# WS2812_MATRIX_9.net
KiCad netlist of a schematic drawn in Altium Designer
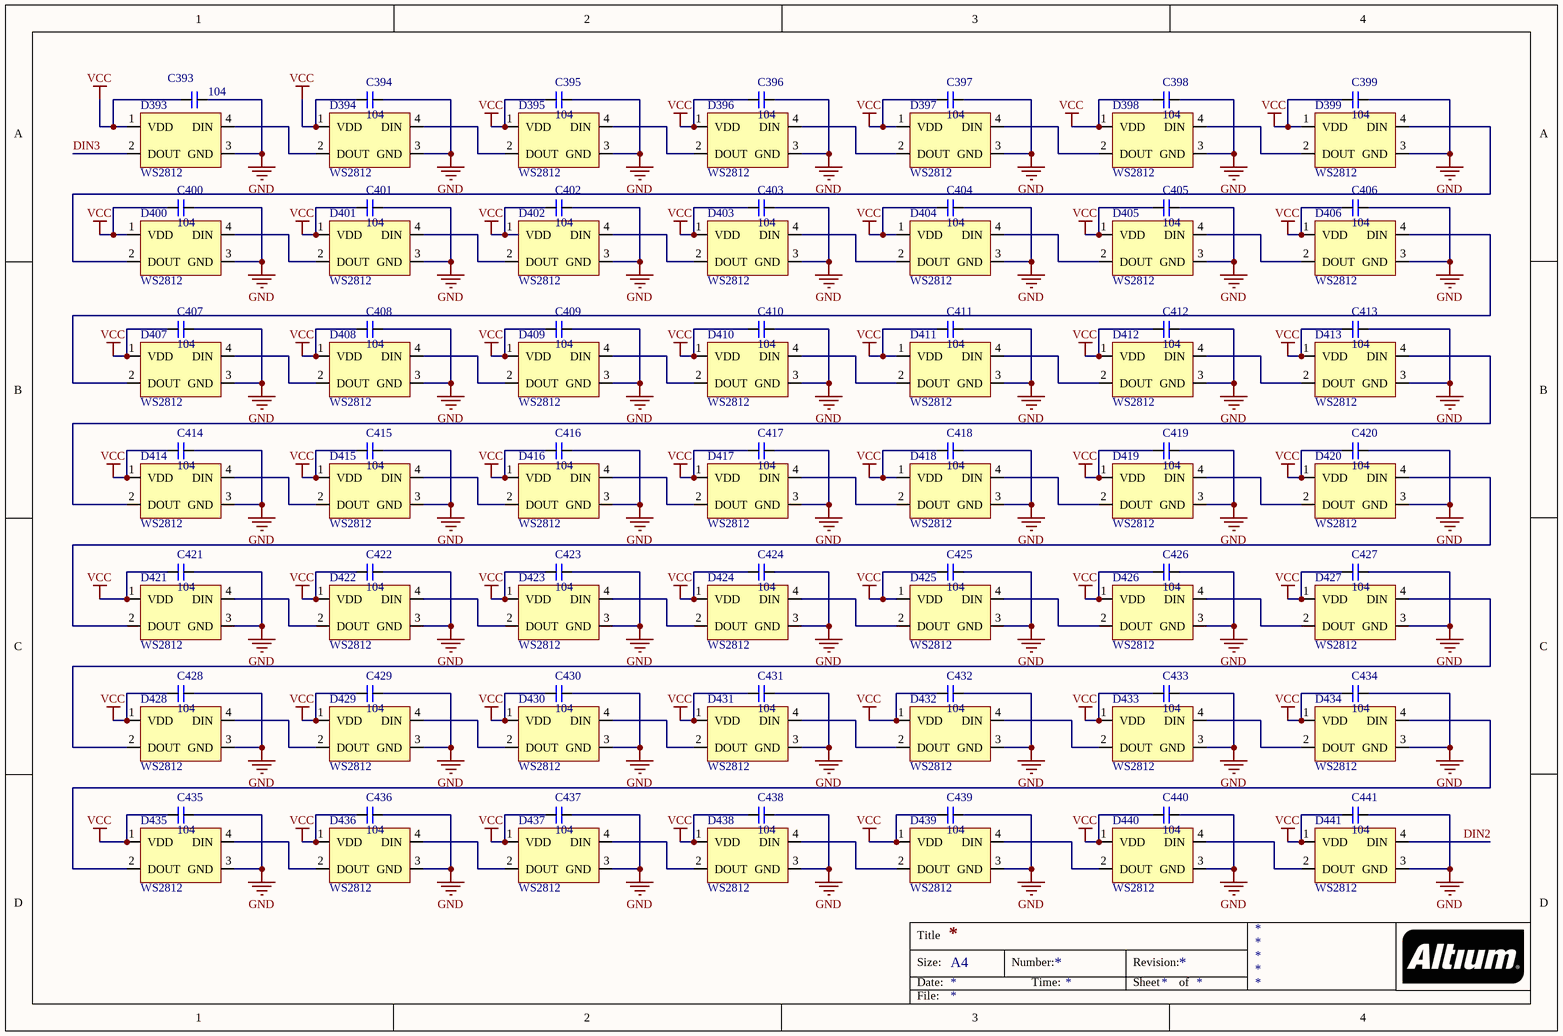
[diagram p0: WS2812_MATRIX_9.SchDoc]

(export (version "E")
  (design (tool "Eeschema 10.0.6"))
  (components
    (comp (ref "C393")
      (value "104")
      (footprint "C0805")
      (description "Cap")
      (libsource (lib "SCH_Bacsic") (part "CAP"))
    )
    (comp (ref "C394")
      (value "104")
      (footprint "C0805")
      (description "Cap")
      (libsource (lib "SCH_Bacsic") (part "CAP"))
    )
    (comp (ref "C395")
      (value "104")
      (footprint "C0805")
      (description "Cap")
      (libsource (lib "SCH_Bacsic") (part "CAP"))
    )
    (comp (ref "C396")
      (value "104")
      (footprint "C0805")
      (description "Cap")
      (libsource (lib "SCH_Bacsic") (part "CAP"))
    )
    (comp (ref "C397")
      (value "104")
      (footprint "C0805")
      (description "Cap")
      (libsource (lib "SCH_Bacsic") (part "CAP"))
    )
    (comp (ref "C398")
      (value "104")
      (footprint "C0805")
      (description "Cap")
      (libsource (lib "SCH_Bacsic") (part "CAP"))
    )
    (comp (ref "C399")
      (value "104")
      (footprint "C0805")
      (description "Cap")
      (libsource (lib "SCH_Bacsic") (part "CAP"))
    )
    (comp (ref "C400")
      (value "104")
      (footprint "C0805")
      (description "Cap")
      (libsource (lib "SCH_Bacsic") (part "CAP"))
    )
    (comp (ref "C401")
      (value "104")
      (footprint "C0805")
      (description "Cap")
      (libsource (lib "SCH_Bacsic") (part "CAP"))
    )
    (comp (ref "C402")
      (value "104")
      (footprint "C0805")
      (description "Cap")
      (libsource (lib "SCH_Bacsic") (part "CAP"))
    )
    (comp (ref "C403")
      (value "104")
      (footprint "C0805")
      (description "Cap")
      (libsource (lib "SCH_Bacsic") (part "CAP"))
    )
    (comp (ref "C404")
      (value "104")
      (footprint "C0805")
      (description "Cap")
      (libsource (lib "SCH_Bacsic") (part "CAP"))
    )
    (comp (ref "C405")
      (value "104")
      (footprint "C0805")
      (description "Cap")
      (libsource (lib "SCH_Bacsic") (part "CAP"))
    )
    (comp (ref "C406")
      (value "104")
      (footprint "C0805")
      (description "Cap")
      (libsource (lib "SCH_Bacsic") (part "CAP"))
    )
    (comp (ref "C407")
      (value "104")
      (footprint "C0805")
      (description "Cap")
      (libsource (lib "SCH_Bacsic") (part "CAP"))
    )
    (comp (ref "C408")
      (value "104")
      (footprint "C0805")
      (description "Cap")
      (libsource (lib "SCH_Bacsic") (part "CAP"))
    )
    (comp (ref "C409")
      (value "104")
      (footprint "C0805")
      (description "Cap")
      (libsource (lib "SCH_Bacsic") (part "CAP"))
    )
    (comp (ref "C410")
      (value "104")
      (footprint "C0805")
      (description "Cap")
      (libsource (lib "SCH_Bacsic") (part "CAP"))
    )
    (comp (ref "C411")
      (value "104")
      (footprint "C0805")
      (description "Cap")
      (libsource (lib "SCH_Bacsic") (part "CAP"))
    )
    (comp (ref "C412")
      (value "104")
      (footprint "C0805")
      (description "Cap")
      (libsource (lib "SCH_Bacsic") (part "CAP"))
    )
    (comp (ref "C413")
      (value "104")
      (footprint "C0805")
      (description "Cap")
      (libsource (lib "SCH_Bacsic") (part "CAP"))
    )
    (comp (ref "C414")
      (value "104")
      (footprint "C0805")
      (description "Cap")
      (libsource (lib "SCH_Bacsic") (part "CAP"))
    )
    (comp (ref "C415")
      (value "104")
      (footprint "C0805")
      (description "Cap")
      (libsource (lib "SCH_Bacsic") (part "CAP"))
    )
    (comp (ref "C416")
      (value "104")
      (footprint "C0805")
      (description "Cap")
      (libsource (lib "SCH_Bacsic") (part "CAP"))
    )
    (comp (ref "C417")
      (value "104")
      (footprint "C0805")
      (description "Cap")
      (libsource (lib "SCH_Bacsic") (part "CAP"))
    )
    (comp (ref "C418")
      (value "104")
      (footprint "C0805")
      (description "Cap")
      (libsource (lib "SCH_Bacsic") (part "CAP"))
    )
    (comp (ref "C419")
      (value "104")
      (footprint "C0805")
      (description "Cap")
      (libsource (lib "SCH_Bacsic") (part "CAP"))
    )
    (comp (ref "C420")
      (value "104")
      (footprint "C0805")
      (description "Cap")
      (libsource (lib "SCH_Bacsic") (part "CAP"))
    )
    (comp (ref "C421")
      (value "104")
      (footprint "C0805")
      (description "Cap")
      (libsource (lib "SCH_Bacsic") (part "CAP"))
    )
    (comp (ref "C422")
      (value "104")
      (footprint "C0805")
      (description "Cap")
      (libsource (lib "SCH_Bacsic") (part "CAP"))
    )
    (comp (ref "C423")
      (value "104")
      (footprint "C0805")
      (description "Cap")
      (libsource (lib "SCH_Bacsic") (part "CAP"))
    )
    (comp (ref "C424")
      (value "104")
      (footprint "C0805")
      (description "Cap")
      (libsource (lib "SCH_Bacsic") (part "CAP"))
    )
    (comp (ref "C425")
      (value "104")
      (footprint "C0805")
      (description "Cap")
      (libsource (lib "SCH_Bacsic") (part "CAP"))
    )
    (comp (ref "C426")
      (value "104")
      (footprint "C0805")
      (description "Cap")
      (libsource (lib "SCH_Bacsic") (part "CAP"))
    )
    (comp (ref "C427")
      (value "104")
      (footprint "C0805")
      (description "Cap")
      (libsource (lib "SCH_Bacsic") (part "CAP"))
    )
    (comp (ref "C428")
      (value "104")
      (footprint "C0805")
      (description "Cap")
      (libsource (lib "SCH_Bacsic") (part "CAP"))
    )
    (comp (ref "C429")
      (value "104")
      (footprint "C0805")
      (description "Cap")
      (libsource (lib "SCH_Bacsic") (part "CAP"))
    )
    (comp (ref "C430")
      (value "104")
      (footprint "C0805")
      (description "Cap")
      (libsource (lib "SCH_Bacsic") (part "CAP"))
    )
    (comp (ref "C431")
      (value "104")
      (footprint "C0805")
      (description "Cap")
      (libsource (lib "SCH_Bacsic") (part "CAP"))
    )
    (comp (ref "C432")
      (value "104")
      (footprint "C0805")
      (description "Cap")
      (libsource (lib "SCH_Bacsic") (part "CAP"))
    )
    (comp (ref "C433")
      (value "104")
      (footprint "C0805")
      (description "Cap")
      (libsource (lib "SCH_Bacsic") (part "CAP"))
    )
    (comp (ref "C434")
      (value "104")
      (footprint "C0805")
      (description "Cap")
      (libsource (lib "SCH_Bacsic") (part "CAP"))
    )
    (comp (ref "C435")
      (value "104")
      (footprint "C0805")
      (description "Cap")
      (libsource (lib "SCH_Bacsic") (part "CAP"))
    )
    (comp (ref "C436")
      (value "104")
      (footprint "C0805")
      (description "Cap")
      (libsource (lib "SCH_Bacsic") (part "CAP"))
    )
    (comp (ref "C437")
      (value "104")
      (footprint "C0805")
      (description "Cap")
      (libsource (lib "SCH_Bacsic") (part "CAP"))
    )
    (comp (ref "C438")
      (value "104")
      (footprint "C0805")
      (description "Cap")
      (libsource (lib "SCH_Bacsic") (part "CAP"))
    )
    (comp (ref "C439")
      (value "104")
      (footprint "C0805")
      (description "Cap")
      (libsource (lib "SCH_Bacsic") (part "CAP"))
    )
    (comp (ref "C440")
      (value "104")
      (footprint "C0805")
      (description "Cap")
      (libsource (lib "SCH_Bacsic") (part "CAP"))
    )
    (comp (ref "C441")
      (value "104")
      (footprint "C0805")
      (description "Cap")
      (libsource (lib "SCH_Bacsic") (part "CAP"))
    )
    (comp (ref "D393")
      (value "WS2812")
      (footprint "WS2812_3528")
      (libsource (lib "SCH_Bacsic") (part "WS2812"))
    )
    (comp (ref "D394")
      (value "WS2812")
      (footprint "WS2812_3528")
      (libsource (lib "SCH_Bacsic") (part "WS2812"))
    )
    (comp (ref "D395")
      (value "WS2812")
      (footprint "WS2812_3528")
      (libsource (lib "SCH_Bacsic") (part "WS2812"))
    )
    (comp (ref "D396")
      (value "WS2812")
      (footprint "WS2812_3528")
      (libsource (lib "SCH_Bacsic") (part "WS2812"))
    )
    (comp (ref "D397")
      (value "WS2812")
      (footprint "WS2812_3528")
      (libsource (lib "SCH_Bacsic") (part "WS2812"))
    )
    (comp (ref "D398")
      (value "WS2812")
      (footprint "WS2812_3528")
      (libsource (lib "SCH_Bacsic") (part "WS2812"))
    )
    (comp (ref "D399")
      (value "WS2812")
      (footprint "WS2812_3528")
      (libsource (lib "SCH_Bacsic") (part "WS2812"))
    )
    (comp (ref "D400")
      (value "WS2812")
      (footprint "WS2812_3528")
      (libsource (lib "SCH_Bacsic") (part "WS2812"))
    )
    (comp (ref "D401")
      (value "WS2812")
      (footprint "WS2812_3528")
      (libsource (lib "SCH_Bacsic") (part "WS2812"))
    )
    (comp (ref "D402")
      (value "WS2812")
      (footprint "WS2812_3528")
      (libsource (lib "SCH_Bacsic") (part "WS2812"))
    )
    (comp (ref "D403")
      (value "WS2812")
      (footprint "WS2812_3528")
      (libsource (lib "SCH_Bacsic") (part "WS2812"))
    )
    (comp (ref "D404")
      (value "WS2812")
      (footprint "WS2812_3528")
      (libsource (lib "SCH_Bacsic") (part "WS2812"))
    )
    (comp (ref "D405")
      (value "WS2812")
      (footprint "WS2812_3528")
      (libsource (lib "SCH_Bacsic") (part "WS2812"))
    )
    (comp (ref "D406")
      (value "WS2812")
      (footprint "WS2812_3528")
      (libsource (lib "SCH_Bacsic") (part "WS2812"))
    )
    (comp (ref "D407")
      (value "WS2812")
      (footprint "WS2812_3528")
      (libsource (lib "SCH_Bacsic") (part "WS2812"))
    )
    (comp (ref "D408")
      (value "WS2812")
      (footprint "WS2812_3528")
      (libsource (lib "SCH_Bacsic") (part "WS2812"))
    )
    (comp (ref "D409")
      (value "WS2812")
      (footprint "WS2812_3528")
      (libsource (lib "SCH_Bacsic") (part "WS2812"))
    )
    (comp (ref "D410")
      (value "WS2812")
      (footprint "WS2812_3528")
      (libsource (lib "SCH_Bacsic") (part "WS2812"))
    )
    (comp (ref "D411")
      (value "WS2812")
      (footprint "WS2812_3528")
      (libsource (lib "SCH_Bacsic") (part "WS2812"))
    )
    (comp (ref "D412")
      (value "WS2812")
      (footprint "WS2812_3528")
      (libsource (lib "SCH_Bacsic") (part "WS2812"))
    )
    (comp (ref "D413")
      (value "WS2812")
      (footprint "WS2812_3528")
      (libsource (lib "SCH_Bacsic") (part "WS2812"))
    )
    (comp (ref "D414")
      (value "WS2812")
      (footprint "WS2812_3528")
      (libsource (lib "SCH_Bacsic") (part "WS2812"))
    )
    (comp (ref "D415")
      (value "WS2812")
      (footprint "WS2812_3528")
      (libsource (lib "SCH_Bacsic") (part "WS2812"))
    )
    (comp (ref "D416")
      (value "WS2812")
      (footprint "WS2812_3528")
      (libsource (lib "SCH_Bacsic") (part "WS2812"))
    )
    (comp (ref "D417")
      (value "WS2812")
      (footprint "WS2812_3528")
      (libsource (lib "SCH_Bacsic") (part "WS2812"))
    )
    (comp (ref "D418")
      (value "WS2812")
      (footprint "WS2812_3528")
      (libsource (lib "SCH_Bacsic") (part "WS2812"))
    )
    (comp (ref "D419")
      (value "WS2812")
      (footprint "WS2812_3528")
      (libsource (lib "SCH_Bacsic") (part "WS2812"))
    )
    (comp (ref "D420")
      (value "WS2812")
      (footprint "WS2812_3528")
      (libsource (lib "SCH_Bacsic") (part "WS2812"))
    )
    (comp (ref "D421")
      (value "WS2812")
      (footprint "WS2812_3528")
      (libsource (lib "SCH_Bacsic") (part "WS2812"))
    )
    (comp (ref "D422")
      (value "WS2812")
      (footprint "WS2812_3528")
      (libsource (lib "SCH_Bacsic") (part "WS2812"))
    )
    (comp (ref "D423")
      (value "WS2812")
      (footprint "WS2812_3528")
      (libsource (lib "SCH_Bacsic") (part "WS2812"))
    )
    (comp (ref "D424")
      (value "WS2812")
      (footprint "WS2812_3528")
      (libsource (lib "SCH_Bacsic") (part "WS2812"))
    )
    (comp (ref "D425")
      (value "WS2812")
      (footprint "WS2812_3528")
      (libsource (lib "SCH_Bacsic") (part "WS2812"))
    )
    (comp (ref "D426")
      (value "WS2812")
      (footprint "WS2812_3528")
      (libsource (lib "SCH_Bacsic") (part "WS2812"))
    )
    (comp (ref "D427")
      (value "WS2812")
      (footprint "WS2812_3528")
      (libsource (lib "SCH_Bacsic") (part "WS2812"))
    )
    (comp (ref "D428")
      (value "WS2812")
      (footprint "WS2812_3528")
      (libsource (lib "SCH_Bacsic") (part "WS2812"))
    )
    (comp (ref "D429")
      (value "WS2812")
      (footprint "WS2812_3528")
      (libsource (lib "SCH_Bacsic") (part "WS2812"))
    )
    (comp (ref "D430")
      (value "WS2812")
      (footprint "WS2812_3528")
      (libsource (lib "SCH_Bacsic") (part "WS2812"))
    )
    (comp (ref "D431")
      (value "WS2812")
      (footprint "WS2812_3528")
      (libsource (lib "SCH_Bacsic") (part "WS2812"))
    )
    (comp (ref "D432")
      (value "WS2812")
      (footprint "WS2812_3528")
      (libsource (lib "SCH_Bacsic") (part "WS2812"))
    )
    (comp (ref "D433")
      (value "WS2812")
      (footprint "WS2812_3528")
      (libsource (lib "SCH_Bacsic") (part "WS2812"))
    )
    (comp (ref "D434")
      (value "WS2812")
      (footprint "WS2812_3528")
      (libsource (lib "SCH_Bacsic") (part "WS2812"))
    )
    (comp (ref "D435")
      (value "WS2812")
      (footprint "WS2812_3528")
      (libsource (lib "SCH_Bacsic") (part "WS2812"))
    )
    (comp (ref "D436")
      (value "WS2812")
      (footprint "WS2812_3528")
      (libsource (lib "SCH_Bacsic") (part "WS2812"))
    )
    (comp (ref "D437")
      (value "WS2812")
      (footprint "WS2812_3528")
      (libsource (lib "SCH_Bacsic") (part "WS2812"))
    )
    (comp (ref "D438")
      (value "WS2812")
      (footprint "WS2812_3528")
      (libsource (lib "SCH_Bacsic") (part "WS2812"))
    )
    (comp (ref "D439")
      (value "WS2812")
      (footprint "WS2812_3528")
      (libsource (lib "SCH_Bacsic") (part "WS2812"))
    )
    (comp (ref "D440")
      (value "WS2812")
      (footprint "WS2812_3528")
      (libsource (lib "SCH_Bacsic") (part "WS2812"))
    )
    (comp (ref "D441")
      (value "WS2812")
      (footprint "WS2812_3528")
      (libsource (lib "SCH_Bacsic") (part "WS2812"))
    )
  )
  (nets
    (net (code "1") (name "/DIN2") (class "Default")
      (node (ref "D441") (pin "4") (pinfunction "DIN_4") (pintype "passive"))
    )
    (net (code "2") (name "/DIN3") (class "Default")
      (node (ref "D393") (pin "2") (pinfunction "DOUT_2") (pintype "passive"))
    )
    (net (code "3") (name "GND") (class "Default")
      (node (ref "C393") (pin "2") (pintype "passive"))
      (node (ref "C394") (pin "1") (pintype "passive"))
      (node (ref "C395") (pin "1") (pintype "passive"))
      (node (ref "C396") (pin "1") (pintype "passive"))
      (node (ref "C397") (pin "1") (pintype "passive"))
      (node (ref "C398") (pin "1") (pintype "passive"))
      (node (ref "C399") (pin "1") (pintype "passive"))
      (node (ref "C400") (pin "1") (pintype "passive"))
      (node (ref "C401") (pin "1") (pintype "passive"))
      (node (ref "C402") (pin "1") (pintype "passive"))
      (node (ref "C403") (pin "1") (pintype "passive"))
      (node (ref "C404") (pin "1") (pintype "passive"))
      (node (ref "C405") (pin "1") (pintype "passive"))
      (node (ref "C406") (pin "1") (pintype "passive"))
      (node (ref "C407") (pin "1") (pintype "passive"))
      (node (ref "C408") (pin "1") (pintype "passive"))
      (node (ref "C409") (pin "1") (pintype "passive"))
      (node (ref "C410") (pin "1") (pintype "passive"))
      (node (ref "C411") (pin "1") (pintype "passive"))
      (node (ref "C412") (pin "1") (pintype "passive"))
      (node (ref "C413") (pin "1") (pintype "passive"))
      (node (ref "C414") (pin "1") (pintype "passive"))
      (node (ref "C415") (pin "1") (pintype "passive"))
      (node (ref "C416") (pin "1") (pintype "passive"))
      (node (ref "C417") (pin "1") (pintype "passive"))
      (node (ref "C418") (pin "1") (pintype "passive"))
      (node (ref "C419") (pin "1") (pintype "passive"))
      (node (ref "C420") (pin "1") (pintype "passive"))
      (node (ref "C421") (pin "1") (pintype "passive"))
      (node (ref "C422") (pin "1") (pintype "passive"))
      (node (ref "C423") (pin "1") (pintype "passive"))
      (node (ref "C424") (pin "1") (pintype "passive"))
      (node (ref "C425") (pin "1") (pintype "passive"))
      (node (ref "C426") (pin "1") (pintype "passive"))
      (node (ref "C427") (pin "1") (pintype "passive"))
      (node (ref "C428") (pin "1") (pintype "passive"))
      (node (ref "C429") (pin "1") (pintype "passive"))
      (node (ref "C430") (pin "1") (pintype "passive"))
      (node (ref "C431") (pin "1") (pintype "passive"))
      (node (ref "C432") (pin "1") (pintype "passive"))
      (node (ref "C433") (pin "1") (pintype "passive"))
      (node (ref "C434") (pin "1") (pintype "passive"))
      (node (ref "C435") (pin "1") (pintype "passive"))
      (node (ref "C436") (pin "1") (pintype "passive"))
      (node (ref "C437") (pin "1") (pintype "passive"))
      (node (ref "C438") (pin "1") (pintype "passive"))
      (node (ref "C439") (pin "1") (pintype "passive"))
      (node (ref "C440") (pin "1") (pintype "passive"))
      (node (ref "C441") (pin "1") (pintype "passive"))
      (node (ref "D393") (pin "3") (pinfunction "GND_3") (pintype "passive"))
      (node (ref "D394") (pin "3") (pinfunction "GND_3") (pintype "passive"))
      (node (ref "D395") (pin "3") (pinfunction "GND_3") (pintype "passive"))
      (node (ref "D396") (pin "3") (pinfunction "GND_3") (pintype "passive"))
      (node (ref "D397") (pin "3") (pinfunction "GND_3") (pintype "passive"))
      (node (ref "D398") (pin "3") (pinfunction "GND_3") (pintype "passive"))
      (node (ref "D399") (pin "3") (pinfunction "GND_3") (pintype "passive"))
      (node (ref "D400") (pin "3") (pinfunction "GND_3") (pintype "passive"))
      (node (ref "D401") (pin "3") (pinfunction "GND_3") (pintype "passive"))
      (node (ref "D402") (pin "3") (pinfunction "GND_3") (pintype "passive"))
      (node (ref "D403") (pin "3") (pinfunction "GND_3") (pintype "passive"))
      (node (ref "D404") (pin "3") (pinfunction "GND_3") (pintype "passive"))
      (node (ref "D405") (pin "3") (pinfunction "GND_3") (pintype "passive"))
      (node (ref "D406") (pin "3") (pinfunction "GND_3") (pintype "passive"))
      (node (ref "D407") (pin "3") (pinfunction "GND_3") (pintype "passive"))
      (node (ref "D408") (pin "3") (pinfunction "GND_3") (pintype "passive"))
      (node (ref "D409") (pin "3") (pinfunction "GND_3") (pintype "passive"))
      (node (ref "D410") (pin "3") (pinfunction "GND_3") (pintype "passive"))
      (node (ref "D411") (pin "3") (pinfunction "GND_3") (pintype "passive"))
      (node (ref "D412") (pin "3") (pinfunction "GND_3") (pintype "passive"))
      (node (ref "D413") (pin "3") (pinfunction "GND_3") (pintype "passive"))
      (node (ref "D414") (pin "3") (pinfunction "GND_3") (pintype "passive"))
      (node (ref "D415") (pin "3") (pinfunction "GND_3") (pintype "passive"))
      (node (ref "D416") (pin "3") (pinfunction "GND_3") (pintype "passive"))
      (node (ref "D417") (pin "3") (pinfunction "GND_3") (pintype "passive"))
      (node (ref "D418") (pin "3") (pinfunction "GND_3") (pintype "passive"))
      (node (ref "D419") (pin "3") (pinfunction "GND_3") (pintype "passive"))
      (node (ref "D420") (pin "3") (pinfunction "GND_3") (pintype "passive"))
      (node (ref "D421") (pin "3") (pinfunction "GND_3") (pintype "passive"))
      (node (ref "D422") (pin "3") (pinfunction "GND_3") (pintype "passive"))
      (node (ref "D423") (pin "3") (pinfunction "GND_3") (pintype "passive"))
      (node (ref "D424") (pin "3") (pinfunction "GND_3") (pintype "passive"))
      (node (ref "D425") (pin "3") (pinfunction "GND_3") (pintype "passive"))
      (node (ref "D426") (pin "3") (pinfunction "GND_3") (pintype "passive"))
      (node (ref "D427") (pin "3") (pinfunction "GND_3") (pintype "passive"))
      (node (ref "D428") (pin "3") (pinfunction "GND_3") (pintype "passive"))
      (node (ref "D429") (pin "3") (pinfunction "GND_3") (pintype "passive"))
      (node (ref "D430") (pin "3") (pinfunction "GND_3") (pintype "passive"))
      (node (ref "D431") (pin "3") (pinfunction "GND_3") (pintype "passive"))
      (node (ref "D432") (pin "3") (pinfunction "GND_3") (pintype "passive"))
      (node (ref "D433") (pin "3") (pinfunction "GND_3") (pintype "passive"))
      (node (ref "D434") (pin "3") (pinfunction "GND_3") (pintype "passive"))
      (node (ref "D435") (pin "3") (pinfunction "GND_3") (pintype "passive"))
      (node (ref "D436") (pin "3") (pinfunction "GND_3") (pintype "passive"))
      (node (ref "D437") (pin "3") (pinfunction "GND_3") (pintype "passive"))
      (node (ref "D438") (pin "3") (pinfunction "GND_3") (pintype "passive"))
      (node (ref "D439") (pin "3") (pinfunction "GND_3") (pintype "passive"))
      (node (ref "D440") (pin "3") (pinfunction "GND_3") (pintype "passive"))
      (node (ref "D441") (pin "3") (pinfunction "GND_3") (pintype "passive"))
    )
    (net (code "4") (name "Net-(D393-DIN)") (class "Default")
      (node (ref "D393") (pin "4") (pinfunction "DIN_4") (pintype "passive"))
      (node (ref "D394") (pin "2") (pinfunction "DOUT_2") (pintype "passive"))
    )
    (net (code "5") (name "Net-(D394-DIN)") (class "Default")
      (node (ref "D394") (pin "4") (pinfunction "DIN_4") (pintype "passive"))
      (node (ref "D395") (pin "2") (pinfunction "DOUT_2") (pintype "passive"))
    )
    (net (code "6") (name "Net-(D395-DIN)") (class "Default")
      (node (ref "D395") (pin "4") (pinfunction "DIN_4") (pintype "passive"))
      (node (ref "D396") (pin "2") (pinfunction "DOUT_2") (pintype "passive"))
    )
    (net (code "7") (name "Net-(D396-DIN)") (class "Default")
      (node (ref "D396") (pin "4") (pinfunction "DIN_4") (pintype "passive"))
      (node (ref "D397") (pin "2") (pinfunction "DOUT_2") (pintype "passive"))
    )
    (net (code "8") (name "Net-(D397-DIN)") (class "Default")
      (node (ref "D397") (pin "4") (pinfunction "DIN_4") (pintype "passive"))
      (node (ref "D398") (pin "2") (pinfunction "DOUT_2") (pintype "passive"))
    )
    (net (code "9") (name "Net-(D398-DIN)") (class "Default")
      (node (ref "D398") (pin "4") (pinfunction "DIN_4") (pintype "passive"))
      (node (ref "D399") (pin "2") (pinfunction "DOUT_2") (pintype "passive"))
    )
    (net (code "10") (name "Net-(D399-DIN)") (class "Default")
      (node (ref "D399") (pin "4") (pinfunction "DIN_4") (pintype "passive"))
      (node (ref "D400") (pin "2") (pinfunction "DOUT_2") (pintype "passive"))
    )
    (net (code "11") (name "Net-(D400-DIN)") (class "Default")
      (node (ref "D400") (pin "4") (pinfunction "DIN_4") (pintype "passive"))
      (node (ref "D401") (pin "2") (pinfunction "DOUT_2") (pintype "passive"))
    )
    (net (code "12") (name "Net-(D401-DIN)") (class "Default")
      (node (ref "D401") (pin "4") (pinfunction "DIN_4") (pintype "passive"))
      (node (ref "D402") (pin "2") (pinfunction "DOUT_2") (pintype "passive"))
    )
    (net (code "13") (name "Net-(D402-DIN)") (class "Default")
      (node (ref "D402") (pin "4") (pinfunction "DIN_4") (pintype "passive"))
      (node (ref "D403") (pin "2") (pinfunction "DOUT_2") (pintype "passive"))
    )
    (net (code "14") (name "Net-(D403-DIN)") (class "Default")
      (node (ref "D403") (pin "4") (pinfunction "DIN_4") (pintype "passive"))
      (node (ref "D404") (pin "2") (pinfunction "DOUT_2") (pintype "passive"))
    )
    (net (code "15") (name "Net-(D404-DIN)") (class "Default")
      (node (ref "D404") (pin "4") (pinfunction "DIN_4") (pintype "passive"))
      (node (ref "D405") (pin "2") (pinfunction "DOUT_2") (pintype "passive"))
    )
    (net (code "16") (name "Net-(D405-DIN)") (class "Default")
      (node (ref "D405") (pin "4") (pinfunction "DIN_4") (pintype "passive"))
      (node (ref "D406") (pin "2") (pinfunction "DOUT_2") (pintype "passive"))
    )
    (net (code "17") (name "Net-(D406-DIN)") (class "Default")
      (node (ref "D406") (pin "4") (pinfunction "DIN_4") (pintype "passive"))
      (node (ref "D407") (pin "2") (pinfunction "DOUT_2") (pintype "passive"))
    )
    (net (code "18") (name "Net-(D407-DIN)") (class "Default")
      (node (ref "D407") (pin "4") (pinfunction "DIN_4") (pintype "passive"))
      (node (ref "D408") (pin "2") (pinfunction "DOUT_2") (pintype "passive"))
    )
    (net (code "19") (name "Net-(D408-DIN)") (class "Default")
      (node (ref "D408") (pin "4") (pinfunction "DIN_4") (pintype "passive"))
      (node (ref "D409") (pin "2") (pinfunction "DOUT_2") (pintype "passive"))
    )
    (net (code "20") (name "Net-(D409-DIN)") (class "Default")
      (node (ref "D409") (pin "4") (pinfunction "DIN_4") (pintype "passive"))
      (node (ref "D410") (pin "2") (pinfunction "DOUT_2") (pintype "passive"))
    )
    (net (code "21") (name "Net-(D410-DIN)") (class "Default")
      (node (ref "D410") (pin "4") (pinfunction "DIN_4") (pintype "passive"))
      (node (ref "D411") (pin "2") (pinfunction "DOUT_2") (pintype "passive"))
    )
    (net (code "22") (name "Net-(D411-DIN)") (class "Default")
      (node (ref "D411") (pin "4") (pinfunction "DIN_4") (pintype "passive"))
      (node (ref "D412") (pin "2") (pinfunction "DOUT_2") (pintype "passive"))
    )
    (net (code "23") (name "Net-(D412-DIN)") (class "Default")
      (node (ref "D412") (pin "4") (pinfunction "DIN_4") (pintype "passive"))
      (node (ref "D413") (pin "2") (pinfunction "DOUT_2") (pintype "passive"))
    )
    (net (code "24") (name "Net-(D413-DIN)") (class "Default")
      (node (ref "D413") (pin "4") (pinfunction "DIN_4") (pintype "passive"))
      (node (ref "D414") (pin "2") (pinfunction "DOUT_2") (pintype "passive"))
    )
    (net (code "25") (name "Net-(D414-DIN)") (class "Default")
      (node (ref "D414") (pin "4") (pinfunction "DIN_4") (pintype "passive"))
      (node (ref "D415") (pin "2") (pinfunction "DOUT_2") (pintype "passive"))
    )
    (net (code "26") (name "Net-(D415-DIN)") (class "Default")
      (node (ref "D415") (pin "4") (pinfunction "DIN_4") (pintype "passive"))
      (node (ref "D416") (pin "2") (pinfunction "DOUT_2") (pintype "passive"))
    )
    (net (code "27") (name "Net-(D416-DIN)") (class "Default")
      (node (ref "D416") (pin "4") (pinfunction "DIN_4") (pintype "passive"))
      (node (ref "D417") (pin "2") (pinfunction "DOUT_2") (pintype "passive"))
    )
    (net (code "28") (name "Net-(D417-DIN)") (class "Default")
      (node (ref "D417") (pin "4") (pinfunction "DIN_4") (pintype "passive"))
      (node (ref "D418") (pin "2") (pinfunction "DOUT_2") (pintype "passive"))
    )
    (net (code "29") (name "Net-(D418-DIN)") (class "Default")
      (node (ref "D418") (pin "4") (pinfunction "DIN_4") (pintype "passive"))
      (node (ref "D419") (pin "2") (pinfunction "DOUT_2") (pintype "passive"))
    )
    (net (code "30") (name "Net-(D419-DIN)") (class "Default")
      (node (ref "D419") (pin "4") (pinfunction "DIN_4") (pintype "passive"))
      (node (ref "D420") (pin "2") (pinfunction "DOUT_2") (pintype "passive"))
    )
    (net (code "31") (name "Net-(D420-DIN)") (class "Default")
      (node (ref "D420") (pin "4") (pinfunction "DIN_4") (pintype "passive"))
      (node (ref "D421") (pin "2") (pinfunction "DOUT_2") (pintype "passive"))
    )
    (net (code "32") (name "Net-(D421-DIN)") (class "Default")
      (node (ref "D421") (pin "4") (pinfunction "DIN_4") (pintype "passive"))
      (node (ref "D422") (pin "2") (pinfunction "DOUT_2") (pintype "passive"))
    )
    (net (code "33") (name "Net-(D422-DIN)") (class "Default")
      (node (ref "D422") (pin "4") (pinfunction "DIN_4") (pintype "passive"))
      (node (ref "D423") (pin "2") (pinfunction "DOUT_2") (pintype "passive"))
    )
    (net (code "34") (name "Net-(D423-DIN)") (class "Default")
      (node (ref "D423") (pin "4") (pinfunction "DIN_4") (pintype "passive"))
      (node (ref "D424") (pin "2") (pinfunction "DOUT_2") (pintype "passive"))
    )
    (net (code "35") (name "Net-(D424-DIN)") (class "Default")
      (node (ref "D424") (pin "4") (pinfunction "DIN_4") (pintype "passive"))
      (node (ref "D425") (pin "2") (pinfunction "DOUT_2") (pintype "passive"))
    )
    (net (code "36") (name "Net-(D425-DIN)") (class "Default")
      (node (ref "D425") (pin "4") (pinfunction "DIN_4") (pintype "passive"))
      (node (ref "D426") (pin "2") (pinfunction "DOUT_2") (pintype "passive"))
    )
    (net (code "37") (name "Net-(D426-DIN)") (class "Default")
      (node (ref "D426") (pin "4") (pinfunction "DIN_4") (pintype "passive"))
      (node (ref "D427") (pin "2") (pinfunction "DOUT_2") (pintype "passive"))
    )
    (net (code "38") (name "Net-(D427-DIN)") (class "Default")
      (node (ref "D427") (pin "4") (pinfunction "DIN_4") (pintype "passive"))
      (node (ref "D428") (pin "2") (pinfunction "DOUT_2") (pintype "passive"))
    )
    (net (code "39") (name "Net-(D428-DIN)") (class "Default")
      (node (ref "D428") (pin "4") (pinfunction "DIN_4") (pintype "passive"))
      (node (ref "D429") (pin "2") (pinfunction "DOUT_2") (pintype "passive"))
    )
    (net (code "40") (name "Net-(D429-DIN)") (class "Default")
      (node (ref "D429") (pin "4") (pinfunction "DIN_4") (pintype "passive"))
      (node (ref "D430") (pin "2") (pinfunction "DOUT_2") (pintype "passive"))
    )
    (net (code "41") (name "Net-(D430-DIN)") (class "Default")
      (node (ref "D430") (pin "4") (pinfunction "DIN_4") (pintype "passive"))
      (node (ref "D431") (pin "2") (pinfunction "DOUT_2") (pintype "passive"))
    )
    (net (code "42") (name "Net-(D431-DIN)") (class "Default")
      (node (ref "D431") (pin "4") (pinfunction "DIN_4") (pintype "passive"))
      (node (ref "D432") (pin "2") (pinfunction "DOUT_2") (pintype "passive"))
    )
    (net (code "43") (name "Net-(D432-DIN)") (class "Default")
      (node (ref "D432") (pin "4") (pinfunction "DIN_4") (pintype "passive"))
      (node (ref "D433") (pin "2") (pinfunction "DOUT_2") (pintype "passive"))
    )
    (net (code "44") (name "Net-(D433-DIN)") (class "Default")
      (node (ref "D433") (pin "4") (pinfunction "DIN_4") (pintype "passive"))
      (node (ref "D434") (pin "2") (pinfunction "DOUT_2") (pintype "passive"))
    )
    (net (code "45") (name "Net-(D434-DIN)") (class "Default")
      (node (ref "D434") (pin "4") (pinfunction "DIN_4") (pintype "passive"))
      (node (ref "D435") (pin "2") (pinfunction "DOUT_2") (pintype "passive"))
    )
    (net (code "46") (name "Net-(D435-DIN)") (class "Default")
      (node (ref "D435") (pin "4") (pinfunction "DIN_4") (pintype "passive"))
      (node (ref "D436") (pin "2") (pinfunction "DOUT_2") (pintype "passive"))
    )
    (net (code "47") (name "Net-(D436-DIN)") (class "Default")
      (node (ref "D436") (pin "4") (pinfunction "DIN_4") (pintype "passive"))
      (node (ref "D437") (pin "2") (pinfunction "DOUT_2") (pintype "passive"))
    )
    (net (code "48") (name "Net-(D437-DIN)") (class "Default")
      (node (ref "D437") (pin "4") (pinfunction "DIN_4") (pintype "passive"))
      (node (ref "D438") (pin "2") (pinfunction "DOUT_2") (pintype "passive"))
    )
    (net (code "49") (name "Net-(D438-DIN)") (class "Default")
      (node (ref "D438") (pin "4") (pinfunction "DIN_4") (pintype "passive"))
      (node (ref "D439") (pin "2") (pinfunction "DOUT_2") (pintype "passive"))
    )
    (net (code "50") (name "Net-(D439-DIN)") (class "Default")
      (node (ref "D439") (pin "4") (pinfunction "DIN_4") (pintype "passive"))
      (node (ref "D440") (pin "2") (pinfunction "DOUT_2") (pintype "passive"))
    )
    (net (code "51") (name "Net-(D440-DIN)") (class "Default")
      (node (ref "D440") (pin "4") (pinfunction "DIN_4") (pintype "passive"))
      (node (ref "D441") (pin "2") (pinfunction "DOUT_2") (pintype "passive"))
    )
    (net (code "52") (name "VCC") (class "Default")
      (node (ref "C393") (pin "1") (pintype "passive"))
      (node (ref "C394") (pin "2") (pintype "passive"))
      (node (ref "C395") (pin "2") (pintype "passive"))
      (node (ref "C396") (pin "2") (pintype "passive"))
      (node (ref "C397") (pin "2") (pintype "passive"))
      (node (ref "C398") (pin "2") (pintype "passive"))
      (node (ref "C399") (pin "2") (pintype "passive"))
      (node (ref "C400") (pin "2") (pintype "passive"))
      (node (ref "C401") (pin "2") (pintype "passive"))
      (node (ref "C402") (pin "2") (pintype "passive"))
      (node (ref "C403") (pin "2") (pintype "passive"))
      (node (ref "C404") (pin "2") (pintype "passive"))
      (node (ref "C405") (pin "2") (pintype "passive"))
      (node (ref "C406") (pin "2") (pintype "passive"))
      (node (ref "C407") (pin "2") (pintype "passive"))
      (node (ref "C408") (pin "2") (pintype "passive"))
      (node (ref "C409") (pin "2") (pintype "passive"))
      (node (ref "C410") (pin "2") (pintype "passive"))
      (node (ref "C411") (pin "2") (pintype "passive"))
      (node (ref "C412") (pin "2") (pintype "passive"))
      (node (ref "C413") (pin "2") (pintype "passive"))
      (node (ref "C414") (pin "2") (pintype "passive"))
      (node (ref "C415") (pin "2") (pintype "passive"))
      (node (ref "C416") (pin "2") (pintype "passive"))
      (node (ref "C417") (pin "2") (pintype "passive"))
      (node (ref "C418") (pin "2") (pintype "passive"))
      (node (ref "C419") (pin "2") (pintype "passive"))
      (node (ref "C420") (pin "2") (pintype "passive"))
      (node (ref "C421") (pin "2") (pintype "passive"))
      (node (ref "C422") (pin "2") (pintype "passive"))
      (node (ref "C423") (pin "2") (pintype "passive"))
      (node (ref "C424") (pin "2") (pintype "passive"))
      (node (ref "C425") (pin "2") (pintype "passive"))
      (node (ref "C426") (pin "2") (pintype "passive"))
      (node (ref "C427") (pin "2") (pintype "passive"))
      (node (ref "C428") (pin "2") (pintype "passive"))
      (node (ref "C429") (pin "2") (pintype "passive"))
      (node (ref "C430") (pin "2") (pintype "passive"))
      (node (ref "C431") (pin "2") (pintype "passive"))
      (node (ref "C432") (pin "2") (pintype "passive"))
      (node (ref "C433") (pin "2") (pintype "passive"))
      (node (ref "C434") (pin "2") (pintype "passive"))
      (node (ref "C435") (pin "2") (pintype "passive"))
      (node (ref "C436") (pin "2") (pintype "passive"))
      (node (ref "C437") (pin "2") (pintype "passive"))
      (node (ref "C438") (pin "2") (pintype "passive"))
      (node (ref "C439") (pin "2") (pintype "passive"))
      (node (ref "C440") (pin "2") (pintype "passive"))
      (node (ref "C441") (pin "2") (pintype "passive"))
      (node (ref "D393") (pin "1") (pinfunction "VDD_1") (pintype "passive"))
      (node (ref "D394") (pin "1") (pinfunction "VDD_1") (pintype "passive"))
      (node (ref "D395") (pin "1") (pinfunction "VDD_1") (pintype "passive"))
      (node (ref "D396") (pin "1") (pinfunction "VDD_1") (pintype "passive"))
      (node (ref "D397") (pin "1") (pinfunction "VDD_1") (pintype "passive"))
      (node (ref "D398") (pin "1") (pinfunction "VDD_1") (pintype "passive"))
      (node (ref "D399") (pin "1") (pinfunction "VDD_1") (pintype "passive"))
      (node (ref "D400") (pin "1") (pinfunction "VDD_1") (pintype "passive"))
      (node (ref "D401") (pin "1") (pinfunction "VDD_1") (pintype "passive"))
      (node (ref "D402") (pin "1") (pinfunction "VDD_1") (pintype "passive"))
      (node (ref "D403") (pin "1") (pinfunction "VDD_1") (pintype "passive"))
      (node (ref "D404") (pin "1") (pinfunction "VDD_1") (pintype "passive"))
      (node (ref "D405") (pin "1") (pinfunction "VDD_1") (pintype "passive"))
      (node (ref "D406") (pin "1") (pinfunction "VDD_1") (pintype "passive"))
      (node (ref "D407") (pin "1") (pinfunction "VDD_1") (pintype "passive"))
      (node (ref "D408") (pin "1") (pinfunction "VDD_1") (pintype "passive"))
      (node (ref "D409") (pin "1") (pinfunction "VDD_1") (pintype "passive"))
      (node (ref "D410") (pin "1") (pinfunction "VDD_1") (pintype "passive"))
      (node (ref "D411") (pin "1") (pinfunction "VDD_1") (pintype "passive"))
      (node (ref "D412") (pin "1") (pinfunction "VDD_1") (pintype "passive"))
      (node (ref "D413") (pin "1") (pinfunction "VDD_1") (pintype "passive"))
      (node (ref "D414") (pin "1") (pinfunction "VDD_1") (pintype "passive"))
      (node (ref "D415") (pin "1") (pinfunction "VDD_1") (pintype "passive"))
      (node (ref "D416") (pin "1") (pinfunction "VDD_1") (pintype "passive"))
      (node (ref "D417") (pin "1") (pinfunction "VDD_1") (pintype "passive"))
      (node (ref "D418") (pin "1") (pinfunction "VDD_1") (pintype "passive"))
      (node (ref "D419") (pin "1") (pinfunction "VDD_1") (pintype "passive"))
      (node (ref "D420") (pin "1") (pinfunction "VDD_1") (pintype "passive"))
      (node (ref "D421") (pin "1") (pinfunction "VDD_1") (pintype "passive"))
      (node (ref "D422") (pin "1") (pinfunction "VDD_1") (pintype "passive"))
      (node (ref "D423") (pin "1") (pinfunction "VDD_1") (pintype "passive"))
      (node (ref "D424") (pin "1") (pinfunction "VDD_1") (pintype "passive"))
      (node (ref "D425") (pin "1") (pinfunction "VDD_1") (pintype "passive"))
      (node (ref "D426") (pin "1") (pinfunction "VDD_1") (pintype "passive"))
      (node (ref "D427") (pin "1") (pinfunction "VDD_1") (pintype "passive"))
      (node (ref "D428") (pin "1") (pinfunction "VDD_1") (pintype "passive"))
      (node (ref "D429") (pin "1") (pinfunction "VDD_1") (pintype "passive"))
      (node (ref "D430") (pin "1") (pinfunction "VDD_1") (pintype "passive"))
      (node (ref "D431") (pin "1") (pinfunction "VDD_1") (pintype "passive"))
      (node (ref "D432") (pin "1") (pinfunction "VDD_1") (pintype "passive"))
      (node (ref "D433") (pin "1") (pinfunction "VDD_1") (pintype "passive"))
      (node (ref "D434") (pin "1") (pinfunction "VDD_1") (pintype "passive"))
      (node (ref "D435") (pin "1") (pinfunction "VDD_1") (pintype "passive"))
      (node (ref "D436") (pin "1") (pinfunction "VDD_1") (pintype "passive"))
      (node (ref "D437") (pin "1") (pinfunction "VDD_1") (pintype "passive"))
      (node (ref "D438") (pin "1") (pinfunction "VDD_1") (pintype "passive"))
      (node (ref "D439") (pin "1") (pinfunction "VDD_1") (pintype "passive"))
      (node (ref "D440") (pin "1") (pinfunction "VDD_1") (pintype "passive"))
      (node (ref "D441") (pin "1") (pinfunction "VDD_1") (pintype "passive"))
    )
  )
)
